# -46342_21-004_3_6.net
KiCad netlist of a schematic drawn in Altium Designer
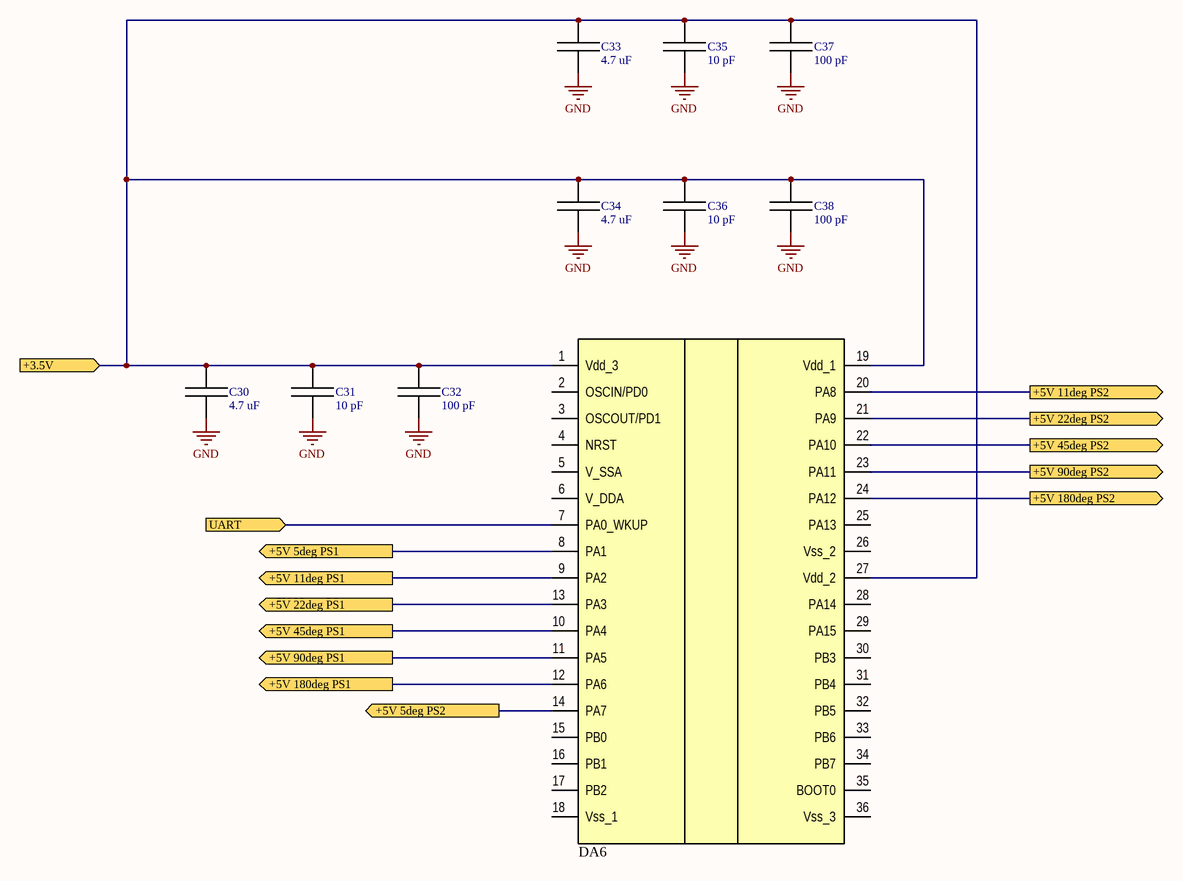
[diagram p0: МПСУ-46342.21-004 Э3 Лист6.SchDoc]

(export (version "E")
  (design (tool "Eeschema 10.0.6"))
  (components
    (comp (ref "C30")
      (value "4.7 uF")
      (footprint "CAPC100X50X55L20N")
      (description "Capacitor, generic")
      (fields (field (name "TOLERANCE") "5 %"))
      (libsource (lib "StudentsLibrary") (part "Capacitor"))
    )
    (comp (ref "C31")
      (value "10 pF")
      (footprint "CAPC100X50X55L20N")
      (description "Capacitor, generic")
      (fields (field (name "TOLERANCE") "5 %"))
      (libsource (lib "StudentsLibrary") (part "Capacitor"))
    )
    (comp (ref "C32")
      (value "100 pF")
      (footprint "CAPC100X50X55L20N")
      (description "Capacitor, generic")
      (fields (field (name "TOLERANCE") "5 %"))
      (libsource (lib "StudentsLibrary") (part "Capacitor"))
    )
    (comp (ref "C33")
      (value "4.7 uF")
      (footprint "CAPC100X50X55L20N")
      (description "Capacitor, generic")
      (fields (field (name "TOLERANCE") "5 %"))
      (libsource (lib "StudentsLibrary") (part "Capacitor"))
    )
    (comp (ref "C34")
      (value "4.7 uF")
      (footprint "CAPC100X50X55L20N")
      (description "Capacitor, generic")
      (fields (field (name "TOLERANCE") "5 %"))
      (libsource (lib "StudentsLibrary") (part "Capacitor"))
    )
    (comp (ref "C35")
      (value "10 pF")
      (footprint "CAPC100X50X55L20N")
      (description "Capacitor, generic")
      (fields (field (name "TOLERANCE") "5 %"))
      (libsource (lib "StudentsLibrary") (part "Capacitor"))
    )
    (comp (ref "C36")
      (value "10 pF")
      (footprint "CAPC100X50X55L20N")
      (description "Capacitor, generic")
      (fields (field (name "TOLERANCE") "5 %"))
      (libsource (lib "StudentsLibrary") (part "Capacitor"))
    )
    (comp (ref "C37")
      (value "100 pF")
      (footprint "CAPC100X50X55L20N")
      (description "Capacitor, generic")
      (fields (field (name "TOLERANCE") "5 %"))
      (libsource (lib "StudentsLibrary") (part "Capacitor"))
    )
    (comp (ref "C38")
      (value "100 pF")
      (footprint "CAPC100X50X55L20N")
      (description "Capacitor, generic")
      (fields (field (name "TOLERANCE") "5 %"))
      (libsource (lib "StudentsLibrary") (part "Capacitor"))
    )
    (comp (ref "DA6")
      (value "~")
      (footprint "QFN50P600X600X90_HS-37N")
      (libsource (lib "receiver") (part "GD32VF103Tx"))
    )
  )
  (nets
    (net (code "1") (name "/+3.5V") (class "Default")
      (node (ref "C30") (pin "2") (pinfunction "2_2") (pintype "passive"))
      (node (ref "C31") (pin "2") (pinfunction "2_2") (pintype "passive"))
      (node (ref "C32") (pin "2") (pinfunction "2_2") (pintype "passive"))
      (node (ref "C33") (pin "2") (pinfunction "2_2") (pintype "passive"))
      (node (ref "C34") (pin "2") (pinfunction "2_2") (pintype "passive"))
      (node (ref "C35") (pin "2") (pinfunction "2_2") (pintype "passive"))
      (node (ref "C36") (pin "2") (pinfunction "2_2") (pintype "passive"))
      (node (ref "C37") (pin "2") (pinfunction "2_2") (pintype "passive"))
      (node (ref "C38") (pin "2") (pinfunction "2_2") (pintype "passive"))
      (node (ref "DA6") (pin "1") (pinfunction "Vdd_3_1") (pintype "passive"))
      (node (ref "DA6") (pin "19") (pinfunction "Vdd_1_19") (pintype "passive"))
      (node (ref "DA6") (pin "27") (pinfunction "Vdd_2_27") (pintype "passive"))
    )
    (net (code "2") (name "/+5V 5deg PS1") (class "Default")
      (node (ref "DA6") (pin "8") (pinfunction "PA1_8") (pintype "passive"))
    )
    (net (code "3") (name "/+5V 5deg PS2") (class "Default")
      (node (ref "DA6") (pin "14") (pinfunction "PA7_14") (pintype "passive"))
    )
    (net (code "4") (name "/+5V 11deg PS1") (class "Default")
      (node (ref "DA6") (pin "9") (pinfunction "PA2_9") (pintype "passive"))
    )
    (net (code "5") (name "/+5V 11deg PS2") (class "Default")
      (node (ref "DA6") (pin "20") (pinfunction "PA8_20") (pintype "passive"))
    )
    (net (code "6") (name "/+5V 22deg PS1") (class "Default")
      (node (ref "DA6") (pin "13") (pinfunction "PA3_13") (pintype "passive"))
    )
    (net (code "7") (name "/+5V 22deg PS2") (class "Default")
      (node (ref "DA6") (pin "21") (pinfunction "PA9_21") (pintype "passive"))
    )
    (net (code "8") (name "/+5V 45deg PS1") (class "Default")
      (node (ref "DA6") (pin "10") (pinfunction "PA4_10") (pintype "passive"))
    )
    (net (code "9") (name "/+5V 45deg PS2") (class "Default")
      (node (ref "DA6") (pin "22") (pinfunction "PA10_22") (pintype "passive"))
    )
    (net (code "10") (name "/+5V 90deg PS1") (class "Default")
      (node (ref "DA6") (pin "11") (pinfunction "PA5_11") (pintype "passive"))
    )
    (net (code "11") (name "/+5V 90deg PS2") (class "Default")
      (node (ref "DA6") (pin "23") (pinfunction "PA11_23") (pintype "passive"))
    )
    (net (code "12") (name "/+5V 180deg PS1") (class "Default")
      (node (ref "DA6") (pin "12") (pinfunction "PA6_12") (pintype "passive"))
    )
    (net (code "13") (name "/+5V 180deg PS2") (class "Default")
      (node (ref "DA6") (pin "24") (pinfunction "PA12_24") (pintype "passive"))
    )
    (net (code "14") (name "/UART") (class "Default")
      (node (ref "DA6") (pin "7") (pinfunction "PA0_WKUP_7") (pintype "passive"))
    )
    (net (code "15") (name "GND") (class "Default")
      (node (ref "C30") (pin "1") (pinfunction "1_1") (pintype "passive"))
      (node (ref "C31") (pin "1") (pinfunction "1_1") (pintype "passive"))
      (node (ref "C32") (pin "1") (pinfunction "1_1") (pintype "passive"))
      (node (ref "C33") (pin "1") (pinfunction "1_1") (pintype "passive"))
      (node (ref "C34") (pin "1") (pinfunction "1_1") (pintype "passive"))
      (node (ref "C35") (pin "1") (pinfunction "1_1") (pintype "passive"))
      (node (ref "C36") (pin "1") (pinfunction "1_1") (pintype "passive"))
      (node (ref "C37") (pin "1") (pinfunction "1_1") (pintype "passive"))
      (node (ref "C38") (pin "1") (pinfunction "1_1") (pintype "passive"))
    )
    (net (code "16") (name "unconnected-(DA6-BOOT0-Pad35)") (class "Default")
      (node (ref "DA6") (pin "35") (pinfunction "BOOT0_35") (pintype "passive"))
    )
    (net (code "17") (name "unconnected-(DA6-NRST-Pad4)") (class "Default")
      (node (ref "DA6") (pin "4") (pinfunction "NRST_4") (pintype "passive"))
    )
    (net (code "18") (name "unconnected-(DA6-OSCIN{slash}PD0-Pad2)") (class "Default")
      (node (ref "DA6") (pin "2") (pinfunction "OSCIN/PD0_2") (pintype "passive"))
    )
    (net (code "19") (name "unconnected-(DA6-OSCOUT{slash}PD1-Pad3)") (class "Default")
      (node (ref "DA6") (pin "3") (pinfunction "OSCOUT/PD1_3") (pintype "passive"))
    )
    (net (code "20") (name "unconnected-(DA6-PA13-Pad25)") (class "Default")
      (node (ref "DA6") (pin "25") (pinfunction "PA13_25") (pintype "passive"))
    )
    (net (code "21") (name "unconnected-(DA6-PA14-Pad28)") (class "Default")
      (node (ref "DA6") (pin "28") (pinfunction "PA14_28") (pintype "passive"))
    )
    (net (code "22") (name "unconnected-(DA6-PA15-Pad29)") (class "Default")
      (node (ref "DA6") (pin "29") (pinfunction "PA15_29") (pintype "passive"))
    )
    (net (code "23") (name "unconnected-(DA6-PB0-Pad15)") (class "Default")
      (node (ref "DA6") (pin "15") (pinfunction "PB0_15") (pintype "passive"))
    )
    (net (code "24") (name "unconnected-(DA6-PB1-Pad16)") (class "Default")
      (node (ref "DA6") (pin "16") (pinfunction "PB1_16") (pintype "passive"))
    )
    (net (code "25") (name "unconnected-(DA6-PB2-Pad17)") (class "Default")
      (node (ref "DA6") (pin "17") (pinfunction "PB2_17") (pintype "passive"))
    )
    (net (code "26") (name "unconnected-(DA6-PB3-Pad30)") (class "Default")
      (node (ref "DA6") (pin "30") (pinfunction "PB3_30") (pintype "passive"))
    )
    (net (code "27") (name "unconnected-(DA6-PB4-Pad31)") (class "Default")
      (node (ref "DA6") (pin "31") (pinfunction "PB4_31") (pintype "passive"))
    )
    (net (code "28") (name "unconnected-(DA6-PB5-Pad32)") (class "Default")
      (node (ref "DA6") (pin "32") (pinfunction "PB5_32") (pintype "passive"))
    )
    (net (code "29") (name "unconnected-(DA6-PB6-Pad33)") (class "Default")
      (node (ref "DA6") (pin "33") (pinfunction "PB6_33") (pintype "passive"))
    )
    (net (code "30") (name "unconnected-(DA6-PB7-Pad34)") (class "Default")
      (node (ref "DA6") (pin "34") (pinfunction "PB7_34") (pintype "passive"))
    )
    (net (code "31") (name "unconnected-(DA6-V_DDA-Pad6)") (class "Default")
      (node (ref "DA6") (pin "6") (pinfunction "V_DDA_6") (pintype "passive"))
    )
    (net (code "32") (name "unconnected-(DA6-V_SSA-Pad5)") (class "Default")
      (node (ref "DA6") (pin "5") (pinfunction "V_SSA_5") (pintype "passive"))
    )
    (net (code "33") (name "unconnected-(DA6-Vss_1-Pad18)") (class "Default")
      (node (ref "DA6") (pin "18") (pinfunction "Vss_1_18") (pintype "passive"))
    )
    (net (code "34") (name "unconnected-(DA6-Vss_2-Pad26)") (class "Default")
      (node (ref "DA6") (pin "26") (pinfunction "Vss_2_26") (pintype "passive"))
    )
    (net (code "35") (name "unconnected-(DA6-Vss_3-Pad36)") (class "Default")
      (node (ref "DA6") (pin "36") (pinfunction "Vss_3_36") (pintype "passive"))
    )
  )
)
